# Power.net
KiCad netlist of a schematic drawn in Altium Designer
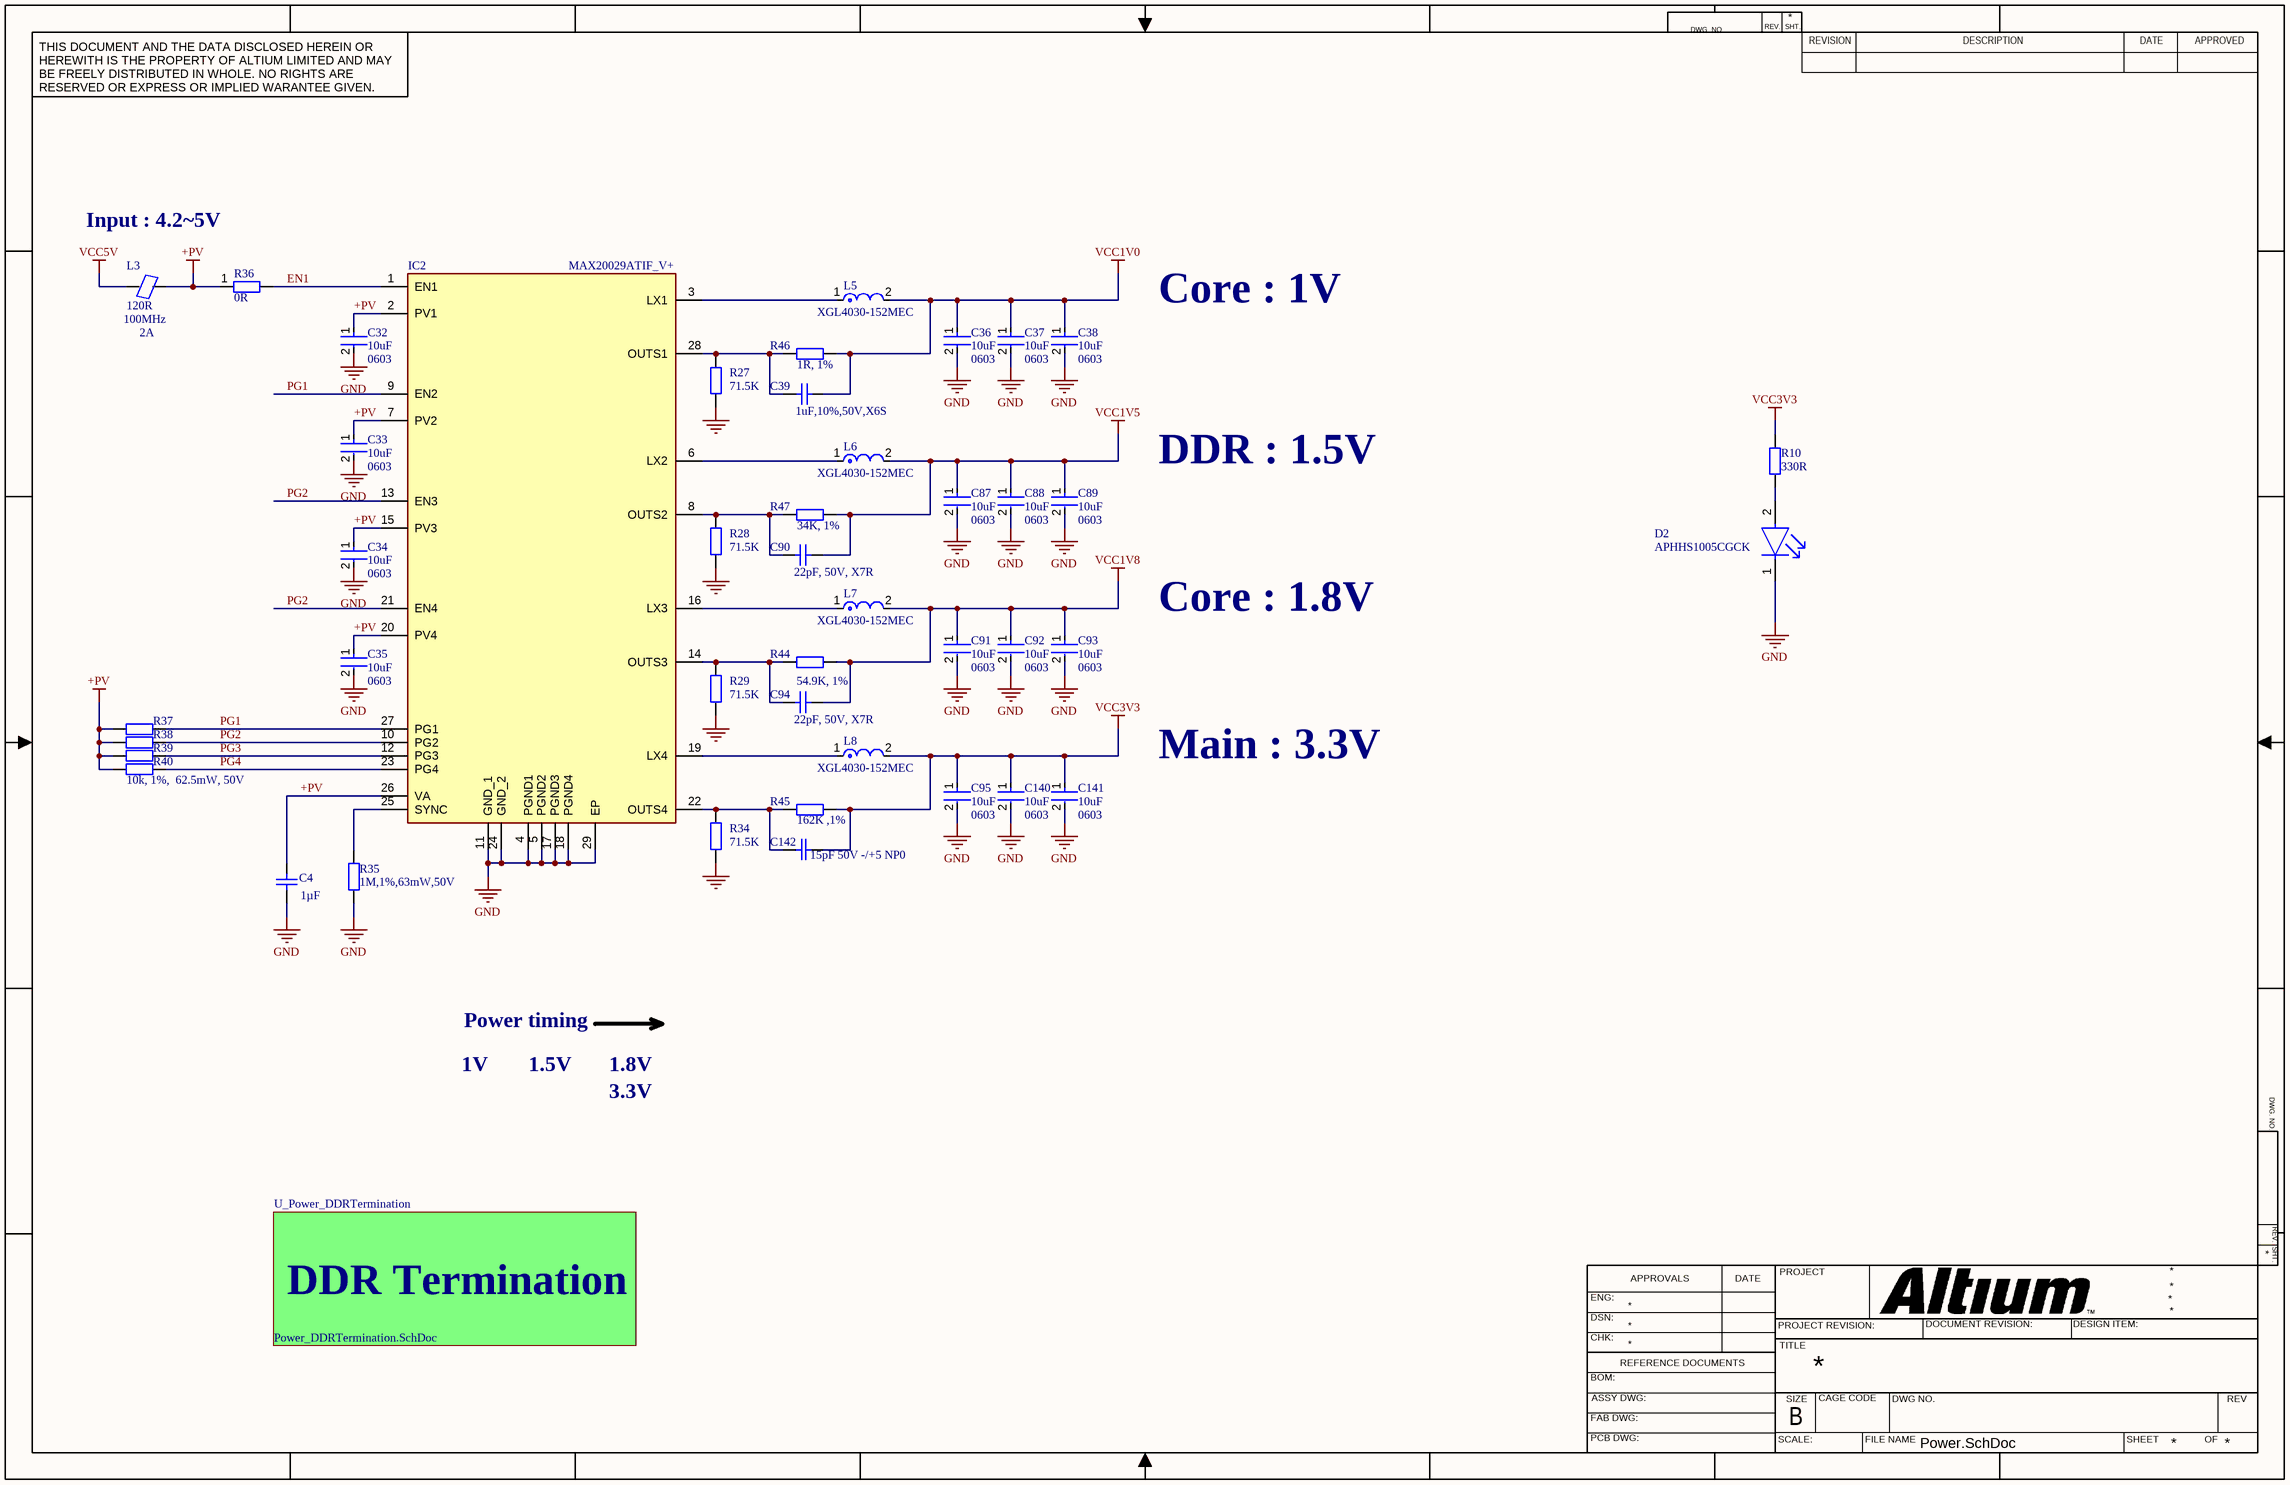
[diagram p0: Power.SchDoc]

(export (version "E")
  (design (tool "Eeschema 10.0.6"))
  (components
    (comp (ref "C4")
      (value "1µF")
      (footprint "CAP0402i")
      (description "0402, 1uF,  10%, 50V, X6S")
      (fields
        (field (name "PART NUMBER") "GRT155C81E105KE13D")
        (field (name "MANUFACTURER") "Murata")
        (field (name "CAPACITANCE") "1µF")
      )
      (libsource (lib "AmpherLib") (part "Cap_1uF_50V_X6S_0402"))
    )
    (comp (ref "C32")
      (value "GRM188R60J106ME47D")
      (footprint "FP-GRM188-0_1-e0_2_0_55-IPC_A")
      (description "Chip Multilayer Ceramic Capacitors for General Purpose, 0603, 10uF, X5R, 15%, 20%, 6.3V")
      (fields
        (field (name "CAPACITANCE") "10uF")
        (field (name "CASE/PACKAGE") "0603")
        (field (name "VOLTAGE") "6.3V")
        (field (name "TOLERANCE") "20%")
      )
      (libsource (lib "Altium Content Vault") (part "02cd4be3c70576c341d710602a673aa"))
    )
    (comp (ref "C33")
      (value "GRM188R60J106ME47D")
      (footprint "FP-GRM188-0_1-e0_2_0_55-IPC_A")
      (description "Chip Multilayer Ceramic Capacitors for General Purpose, 0603, 10uF, X5R, 15%, 20%, 6.3V")
      (fields
        (field (name "CAPACITANCE") "10uF")
        (field (name "CASE/PACKAGE") "0603")
        (field (name "VOLTAGE") "6.3V")
        (field (name "TOLERANCE") "20%")
      )
      (libsource (lib "Altium Content Vault") (part "02cd4be3c70576c341d710602a673aa"))
    )
    (comp (ref "C34")
      (value "GRM188R60J106ME47D")
      (footprint "FP-GRM188-0_1-e0_2_0_55-IPC_A")
      (description "Chip Multilayer Ceramic Capacitors for General Purpose, 0603, 10uF, X5R, 15%, 20%, 6.3V")
      (fields
        (field (name "CAPACITANCE") "10uF")
        (field (name "CASE/PACKAGE") "0603")
        (field (name "VOLTAGE") "6.3V")
        (field (name "TOLERANCE") "20%")
      )
      (libsource (lib "Altium Content Vault") (part "02cd4be3c70576c341d710602a673aa"))
    )
    (comp (ref "C35")
      (value "GRM188R60J106ME47D")
      (footprint "FP-GRM188-0_1-e0_2_0_55-IPC_A")
      (description "Chip Multilayer Ceramic Capacitors for General Purpose, 0603, 10uF, X5R, 15%, 20%, 6.3V")
      (fields
        (field (name "CAPACITANCE") "10uF")
        (field (name "CASE/PACKAGE") "0603")
        (field (name "VOLTAGE") "6.3V")
        (field (name "TOLERANCE") "20%")
      )
      (libsource (lib "Altium Content Vault") (part "02cd4be3c70576c341d710602a673aa"))
    )
    (comp (ref "C36")
      (value "GRM188R60J106ME47D")
      (footprint "FP-GRM188-0_1-e0_2_0_55-IPC_A")
      (description "Chip Multilayer Ceramic Capacitors for General Purpose, 0603, 10uF, X5R, 15%, 20%, 6.3V")
      (fields
        (field (name "CAPACITANCE") "10uF")
        (field (name "CASE/PACKAGE") "0603")
        (field (name "VOLTAGE") "6.3V")
        (field (name "TOLERANCE") "20%")
      )
      (libsource (lib "Altium Content Vault") (part "02cd4be3c70576c341d710602a673aa"))
    )
    (comp (ref "C37")
      (value "GRM188R60J106ME47D")
      (footprint "FP-GRM188-0_1-e0_2_0_55-IPC_A")
      (description "Chip Multilayer Ceramic Capacitors for General Purpose, 0603, 10uF, X5R, 15%, 20%, 6.3V")
      (fields
        (field (name "CAPACITANCE") "10uF")
        (field (name "CASE/PACKAGE") "0603")
        (field (name "VOLTAGE") "6.3V")
        (field (name "TOLERANCE") "20%")
      )
      (libsource (lib "Altium Content Vault") (part "02cd4be3c70576c341d710602a673aa"))
    )
    (comp (ref "C38")
      (value "GRM188R60J106ME47D")
      (footprint "FP-GRM188-0_1-e0_2_0_55-IPC_A")
      (description "Chip Multilayer Ceramic Capacitors for General Purpose, 0603, 10uF, X5R, 15%, 20%, 6.3V")
      (fields
        (field (name "CAPACITANCE") "10uF")
        (field (name "CASE/PACKAGE") "0603")
        (field (name "VOLTAGE") "6.3V")
        (field (name "TOLERANCE") "20%")
      )
      (libsource (lib "Altium Content Vault") (part "02cd4be3c70576c341d710602a673aa"))
    )
    (comp (ref "C39")
      (value "1uF,10%,50V,X6S")
      (footprint "CAP0402i")
      (description "0402, 1uF,  10%, 50V, X6S")
      (fields (field (name "PART NUMBER") "GRT155C81E105KE13D") (field (name "MANUFACTURER") "Murata"))
      (libsource (lib "AmpherLib") (part "Cap_1uF_50V_X6S_0402"))
    )
    (comp (ref "C87")
      (value "GRM188R60J106ME47D")
      (footprint "FP-GRM188-0_1-e0_2_0_55-IPC_A")
      (description "Chip Multilayer Ceramic Capacitors for General Purpose, 0603, 10uF, X5R, 15%, 20%, 6.3V")
      (fields
        (field (name "CAPACITANCE") "10uF")
        (field (name "CASE/PACKAGE") "0603")
        (field (name "VOLTAGE") "6.3V")
        (field (name "TOLERANCE") "20%")
      )
      (libsource (lib "Altium Content Vault") (part "02cd4be3c70576c341d710602a673aa"))
    )
    (comp (ref "C88")
      (value "GRM188R60J106ME47D")
      (footprint "FP-GRM188-0_1-e0_2_0_55-IPC_A")
      (description "Chip Multilayer Ceramic Capacitors for General Purpose, 0603, 10uF, X5R, 15%, 20%, 6.3V")
      (fields
        (field (name "CAPACITANCE") "10uF")
        (field (name "CASE/PACKAGE") "0603")
        (field (name "VOLTAGE") "6.3V")
        (field (name "TOLERANCE") "20%")
      )
      (libsource (lib "Altium Content Vault") (part "02cd4be3c70576c341d710602a673aa"))
    )
    (comp (ref "C89")
      (value "GRM188R60J106ME47D")
      (footprint "FP-GRM188-0_1-e0_2_0_55-IPC_A")
      (description "Chip Multilayer Ceramic Capacitors for General Purpose, 0603, 10uF, X5R, 15%, 20%, 6.3V")
      (fields
        (field (name "CAPACITANCE") "10uF")
        (field (name "CASE/PACKAGE") "0603")
        (field (name "VOLTAGE") "6.3V")
        (field (name "TOLERANCE") "20%")
      )
      (libsource (lib "Altium Content Vault") (part "02cd4be3c70576c341d710602a673aa"))
    )
    (comp (ref "C90")
      (value "22pF, 50V, X7R")
      (footprint "cap0402i")
      (description "Multilayer Ceramic Capacitor, AEC-Q200 CGA Series, 22 pF, - 5%, C0G / NP0, 50 V")
      (fields (field (name "TOLERANCE") "5%") (field (name "PART NUMBER") "CGA2B2C0G1H220J050BA"))
      (libsource (lib "AmpherLib") (part "CAP_22pF_50V_X7R_0402"))
    )
    (comp (ref "C91")
      (value "GRM188R60J106ME47D")
      (footprint "FP-GRM188-0_1-e0_2_0_55-IPC_A")
      (description "Chip Multilayer Ceramic Capacitors for General Purpose, 0603, 10uF, X5R, 15%, 20%, 6.3V")
      (fields
        (field (name "CAPACITANCE") "10uF")
        (field (name "CASE/PACKAGE") "0603")
        (field (name "VOLTAGE") "6.3V")
        (field (name "TOLERANCE") "20%")
      )
      (libsource (lib "Altium Content Vault") (part "02cd4be3c70576c341d710602a673aa"))
    )
    (comp (ref "C92")
      (value "GRM188R60J106ME47D")
      (footprint "FP-GRM188-0_1-e0_2_0_55-IPC_A")
      (description "Chip Multilayer Ceramic Capacitors for General Purpose, 0603, 10uF, X5R, 15%, 20%, 6.3V")
      (fields
        (field (name "CAPACITANCE") "10uF")
        (field (name "CASE/PACKAGE") "0603")
        (field (name "VOLTAGE") "6.3V")
        (field (name "TOLERANCE") "20%")
      )
      (libsource (lib "Altium Content Vault") (part "02cd4be3c70576c341d710602a673aa"))
    )
    (comp (ref "C93")
      (value "GRM188R60J106ME47D")
      (footprint "FP-GRM188-0_1-e0_2_0_55-IPC_A")
      (description "Chip Multilayer Ceramic Capacitors for General Purpose, 0603, 10uF, X5R, 15%, 20%, 6.3V")
      (fields
        (field (name "CAPACITANCE") "10uF")
        (field (name "CASE/PACKAGE") "0603")
        (field (name "VOLTAGE") "6.3V")
        (field (name "TOLERANCE") "20%")
      )
      (libsource (lib "Altium Content Vault") (part "02cd4be3c70576c341d710602a673aa"))
    )
    (comp (ref "C94")
      (value "22pF, 50V, X7R")
      (footprint "cap0402i")
      (description "Multilayer Ceramic Capacitor, AEC-Q200 CGA Series, 22 pF, - 5%, C0G / NP0, 50 V")
      (fields (field (name "TOLERANCE") "5%") (field (name "PART NUMBER") "CGA2B2C0G1H220J050BA"))
      (libsource (lib "AmpherLib") (part "CAP_22pF_50V_X7R_0402"))
    )
    (comp (ref "C95")
      (value "GRM188R60J106ME47D")
      (footprint "FP-GRM188-0_1-e0_2_0_55-IPC_A")
      (description "Chip Multilayer Ceramic Capacitors for General Purpose, 0603, 10uF, X5R, 15%, 20%, 6.3V")
      (fields
        (field (name "CAPACITANCE") "10uF")
        (field (name "CASE/PACKAGE") "0603")
        (field (name "VOLTAGE") "6.3V")
        (field (name "TOLERANCE") "20%")
      )
      (libsource (lib "Altium Content Vault") (part "02cd4be3c70576c341d710602a673aa"))
    )
    (comp (ref "C140")
      (value "GRM188R60J106ME47D")
      (footprint "FP-GRM188-0_1-e0_2_0_55-IPC_A")
      (description "Chip Multilayer Ceramic Capacitors for General Purpose, 0603, 10uF, X5R, 15%, 20%, 6.3V")
      (fields
        (field (name "CAPACITANCE") "10uF")
        (field (name "CASE/PACKAGE") "0603")
        (field (name "VOLTAGE") "6.3V")
        (field (name "TOLERANCE") "20%")
      )
      (libsource (lib "Altium Content Vault") (part "02cd4be3c70576c341d710602a673aa"))
    )
    (comp (ref "C141")
      (value "GRM188R60J106ME47D")
      (footprint "FP-GRM188-0_1-e0_2_0_55-IPC_A")
      (description "Chip Multilayer Ceramic Capacitors for General Purpose, 0603, 10uF, X5R, 15%, 20%, 6.3V")
      (fields
        (field (name "CAPACITANCE") "10uF")
        (field (name "CASE/PACKAGE") "0603")
        (field (name "VOLTAGE") "6.3V")
        (field (name "TOLERANCE") "20%")
      )
      (libsource (lib "Altium Content Vault") (part "02cd4be3c70576c341d710602a673aa"))
    )
    (comp (ref "C142")
      (value "15pF 50V -/+5 NP0")
      (footprint "CAP0402i")
      (description "0402 15 pF 50 V ±5 % Tolerance NP0 SMT Multilayer Ceramic Capacitor")
      (fields (field (name "VOLTAGE") "50V") (field (name "TOLERANCE") "5%"))
      (libsource (lib "AmpherLib") (part "Cap_15pF_50V_0402"))
    )
    (comp (ref "D2")
      (value "APHHS1005CGCK")
      (footprint "FP-APHHS1005CGCK-MFG")
      (description "LED GREEN CLEAR CHIP SMD")
      (libsource (lib "Altium Content Vault") (part "8706943c75ba83719d021d2fdc84c58"))
    )
    (comp (ref "IC2")
      (value "MAX20029ATIF_V+")
      (footprint "PCB1:QFN50P500X500X80-29N")
      (description "DC to DC Converter Quad Step-Down 3V to 5.5V Automotive 28-Pin TQFN Tube")
      (fields
        (field (name "MANUFACTURER_PART_NUMBER") "MAX20029ATIF/V+")
        (field (name "MOUSER PART NUMBER") "700-MAX20029ATIF/V+")
      )
      (libsource (lib "SamacSys") (part "MAX20029ATIF_V+"))
    )
    (comp (ref "L3")
      (value "FB_120@100MHz")
      (footprint "CAP0402i")
      (description "Ferrite Beads Multi-Layer 120Ohm 25% 100MHz 2A 0.055Ohm DCR 0402 T/R")
      (fields
        (field (name "TOLERANCE") "25%")
        (field (name "IMPEDANCE") "120R")
        (field (name "MAX DC CURRENT") "2A")
        (field (name "TEST FREQUENCY") "100MHz")
        (field (name "PART NUMBER") "BLM15PX121SN1D")
      )
      (libsource (lib "AmpherLib") (part "Ferrite Bead_ 0402_120R_100MHz_2A"))
    )
    (comp (ref "L5")
      (value "XGL4030-152MEC")
      (footprint "FP-XGL4030-MFG")
      (description "SHIELDED POWER INDUCTORS, 1.5UH")
      (libsource (lib "Altium Content Vault") (part "4cc4b267dca4c8e51f7102f422741d8"))
    )
    (comp (ref "L6")
      (value "XGL4030-152MEC")
      (footprint "FP-XGL4030-MFG")
      (description "SHIELDED POWER INDUCTORS, 1.5UH")
      (libsource (lib "Altium Content Vault") (part "4cc4b267dca4c8e51f7102f422741d8"))
    )
    (comp (ref "L7")
      (value "XGL4030-152MEC")
      (footprint "FP-XGL4030-MFG")
      (description "SHIELDED POWER INDUCTORS, 1.5UH")
      (libsource (lib "Altium Content Vault") (part "4cc4b267dca4c8e51f7102f422741d8"))
    )
    (comp (ref "L8")
      (value "XGL4030-152MEC")
      (footprint "FP-XGL4030-MFG")
      (description "SHIELDED POWER INDUCTORS, 1.5UH")
      (libsource (lib "Altium Content Vault") (part "4cc4b267dca4c8e51f7102f422741d8"))
    )
    (comp (ref "R10")
      (value "330R")
      (footprint "RES0402i")
      (description "Res Thick Film 0402 330 Ohm 1% 1/16W ±100ppm/°C Molded SMD Paper T/R")
      (fields (field (name "PART NUMBER") "CRCW0402330RFKED") (field (name "VOLTAGE") "50"))
      (libsource (lib "AmpherLib") (part "Res_330R_1%_50V_0402"))
    )
    (comp (ref "R27")
      (value "71.5K")
      (footprint "RES0402i")
      (description "Res Thick Film 0402 71.5K Ohm 1% 1/10W ±100ppm/°C Molded SMD Punched Carrier T/R")
      (fields
        (field (name "PART NUMBER") "ERJ-2RKF7152X")
        (field (name "TOLERANCE") "±1%")
        (field (name "RESISTANCE") "71.5K")
      )
      (libsource (lib "AmpherLib") (part "Res_71.5K_1%_1/10W_0402"))
    )
    (comp (ref "R28")
      (value "71.5K")
      (footprint "RES0402i")
      (description "Res Thick Film 0402 71.5K Ohm 1% 1/10W ±100ppm/°C Molded SMD Punched Carrier T/R")
      (fields
        (field (name "PART NUMBER") "ERJ-2RKF7152X")
        (field (name "TOLERANCE") "±1%")
        (field (name "RESISTANCE") "71.5K")
      )
      (libsource (lib "AmpherLib") (part "Res_71.5K_1%_1/10W_0402"))
    )
    (comp (ref "R29")
      (value "71.5K")
      (footprint "RES0402i")
      (description "Res Thick Film 0402 71.5K Ohm 1% 1/10W ±100ppm/°C Molded SMD Punched Carrier T/R")
      (fields
        (field (name "PART NUMBER") "ERJ-2RKF7152X")
        (field (name "TOLERANCE") "±1%")
        (field (name "RESISTANCE") "71.5K")
      )
      (libsource (lib "AmpherLib") (part "Res_71.5K_1%_1/10W_0402"))
    )
    (comp (ref "R34")
      (value "71.5K")
      (footprint "RES0402i")
      (description "Res Thick Film 0402 71.5K Ohm 1% 1/10W ±100ppm/°C Molded SMD Punched Carrier T/R")
      (fields
        (field (name "PART NUMBER") "ERJ-2RKF7152X")
        (field (name "TOLERANCE") "±1%")
        (field (name "RESISTANCE") "71.5K")
      )
      (libsource (lib "AmpherLib") (part "Res_71.5K_1%_1/10W_0402"))
    )
    (comp (ref "R35")
      (value "1M,1%,63mW,50V")
      (footprint "RES0402i")
      (description "0402,1M,1%,63mW,50V")
      (fields (field (name "PART NUMBER") "ERJ-2RKF1004X") (field (name "VOLTAGE") "50V"))
      (libsource (lib "AmpherLib") (part "Res_1M_1%_0402"))
    )
    (comp (ref "R36")
      (value "0R")
      (footprint "RES0402i")
      (description "0402, 0R")
      (fields (field (name "PART NUMBER") "CRCW04020000Z0EDC") (field (name "VOLTAGE") "50V"))
      (libsource (lib "AmpherLib") (part "Res_0R_0402"))
    )
    (comp (ref "R37")
      (value "10 kOhms")
      (footprint "RES0402i")
      (description "0402, 10K 1%,  62.5mW, 50V")
      (fields (field (name "PART NUMBER") "CR0402-FX-1002GLF") (field (name "VOLTAGE") "50V"))
      (libsource (lib "AmpherLib") (part "Res_10k_1%_0402"))
    )
    (comp (ref "R38")
      (value "10 kOhms")
      (footprint "RES0402i")
      (description "0402, 10K 1%,  62.5mW, 50V")
      (fields (field (name "PART NUMBER") "CR0402-FX-1002GLF") (field (name "VOLTAGE") "50V"))
      (libsource (lib "AmpherLib") (part "Res_10k_1%_0402"))
    )
    (comp (ref "R39")
      (value "10 kOhms")
      (footprint "RES0402i")
      (description "0402, 10K 1%,  62.5mW, 50V")
      (fields (field (name "PART NUMBER") "CR0402-FX-1002GLF") (field (name "VOLTAGE") "50V"))
      (libsource (lib "AmpherLib") (part "Res_10k_1%_0402"))
    )
    (comp (ref "R40")
      (value "10k, 1%,  62.5mW, 50V")
      (footprint "RES0402i")
      (description "0402, 10K 1%,  62.5mW, 50V")
      (fields (field (name "PART NUMBER") "CR0402-FX-1002GLF") (field (name "VOLTAGE") "50V"))
      (libsource (lib "AmpherLib") (part "Res_10k_1%_0402"))
    )
    (comp (ref "R44")
      (value "54.9K, 1%")
      (footprint "RES0402i")
      (description "SMD Chip Resistor, 54.9 kOhm, ± 1%, 100 mW, 0402 [1005 Metric], Thick Film, Precision")
      (fields (field (name "TOLERANCE") "±1%") (field (name "MANUFACTURER") "Panasonic"))
      (libsource (lib "AmpherLib") (part "Res_A_0402__________________________Template_1_1_1_1_1"))
    )
    (comp (ref "R45")
      (value "162K ,1%")
      (footprint "RES0402i")
      (description "Res Thick Film 0402 162K Ohm 1% 0.1W ±100ppm/°C Molded SMD Punched Carrier T/R")
      (fields (field (name "TOLERANCE") "±1%") (field (name "MANUFACTURER") "Panasonic"))
      (libsource (lib "AmpherLib") (part "Res_A_0402__________________________Template_1_1_1_1_1"))
    )
    (comp (ref "R46")
      (value "1R, 1%")
      (footprint "RES0402i")
      (description "SMD Chip Resistor, 1 Ohm, ± 5%, 63 mW, 0402 [1005 Metric], Thick Film, General Purpose")
      (fields (field (name "TOLERANCE") "±1%") (field (name "MANUFACTURER") "Vishay Dale"))
      (libsource (lib "AmpherLib") (part "Res_A_0402__________________________Template_1_1_1_1_1"))
    )
    (comp (ref "R47")
      (value "34K, 1%")
      (footprint "RES0402i")
      (description "SMD Chip Resistor, 34 kOhm, ± 1%, 63 mW, 0402 [1005 Metric], Thick Film, General Purpose")
      (fields (field (name "TOLERANCE") "±1%") (field (name "MANUFACTURER") "Vishay"))
      (libsource (lib "AmpherLib") (part "Res_A_0402__________________________Template_1_1_1_1_1"))
    )
  )
  (nets
    (net (code "1") (name "+PV") (class "Default")
      (node (ref "C32") (pin "1") (pinfunction "1_1") (pintype "passive"))
      (node (ref "C33") (pin "1") (pinfunction "1_1") (pintype "passive"))
      (node (ref "C34") (pin "1") (pinfunction "1_1") (pintype "passive"))
      (node (ref "C35") (pin "1") (pinfunction "1_1") (pintype "passive"))
      (node (ref "C4") (pin "2") (pinfunction "2_2") (pintype "passive"))
      (node (ref "IC2") (pin "15") (pinfunction "PV3_15") (pintype "passive"))
      (node (ref "IC2") (pin "2") (pinfunction "PV1_2") (pintype "passive"))
      (node (ref "IC2") (pin "20") (pinfunction "PV4_20") (pintype "passive"))
      (node (ref "IC2") (pin "26") (pinfunction "VA_26") (pintype "passive"))
      (node (ref "IC2") (pin "7") (pinfunction "PV2_7") (pintype "passive"))
      (node (ref "L3") (pin "2") (pinfunction "2_2") (pintype "passive"))
      (node (ref "R36") (pin "1") (pinfunction "1_1") (pintype "passive"))
      (node (ref "R37") (pin "1") (pinfunction "1_1") (pintype "passive"))
      (node (ref "R38") (pin "1") (pinfunction "1_1") (pintype "passive"))
      (node (ref "R39") (pin "1") (pinfunction "1_1") (pintype "passive"))
      (node (ref "R40") (pin "1") (pinfunction "1_1") (pintype "passive"))
    )
    (net (code "2") (name "/EN1") (class "Default")
      (node (ref "IC2") (pin "1") (pinfunction "EN1_1") (pintype "passive"))
      (node (ref "R36") (pin "2") (pinfunction "2_2") (pintype "passive"))
    )
    (net (code "3") (name "/PG1") (class "Default")
      (node (ref "IC2") (pin "27") (pinfunction "PG1_27") (pintype "passive"))
      (node (ref "IC2") (pin "9") (pinfunction "EN2_9") (pintype "passive"))
      (node (ref "R37") (pin "2") (pinfunction "2_2") (pintype "passive"))
    )
    (net (code "4") (name "/PG2") (class "Default")
      (node (ref "IC2") (pin "10") (pinfunction "PG2_10") (pintype "passive"))
      (node (ref "IC2") (pin "13") (pinfunction "EN3_13") (pintype "passive"))
      (node (ref "IC2") (pin "21") (pinfunction "EN4_21") (pintype "passive"))
      (node (ref "R38") (pin "2") (pinfunction "2_2") (pintype "passive"))
    )
    (net (code "5") (name "/PG3") (class "Default")
      (node (ref "IC2") (pin "12") (pinfunction "PG3_12") (pintype "passive"))
      (node (ref "R39") (pin "2") (pinfunction "2_2") (pintype "passive"))
    )
    (net (code "6") (name "/PG4") (class "Default")
      (node (ref "IC2") (pin "23") (pinfunction "PG4_23") (pintype "passive"))
      (node (ref "R40") (pin "2") (pinfunction "2_2") (pintype "passive"))
    )
    (net (code "7") (name "GND") (class "Default")
      (node (ref "C140") (pin "2") (pinfunction "2_2") (pintype "passive"))
      (node (ref "C141") (pin "2") (pinfunction "2_2") (pintype "passive"))
      (node (ref "C32") (pin "2") (pinfunction "2_2") (pintype "passive"))
      (node (ref "C33") (pin "2") (pinfunction "2_2") (pintype "passive"))
      (node (ref "C34") (pin "2") (pinfunction "2_2") (pintype "passive"))
      (node (ref "C35") (pin "2") (pinfunction "2_2") (pintype "passive"))
      (node (ref "C36") (pin "2") (pinfunction "2_2") (pintype "passive"))
      (node (ref "C37") (pin "2") (pinfunction "2_2") (pintype "passive"))
      (node (ref "C38") (pin "2") (pinfunction "2_2") (pintype "passive"))
      (node (ref "C4") (pin "1") (pinfunction "1_1") (pintype "passive"))
      (node (ref "C87") (pin "2") (pinfunction "2_2") (pintype "passive"))
      (node (ref "C88") (pin "2") (pinfunction "2_2") (pintype "passive"))
      (node (ref "C89") (pin "2") (pinfunction "2_2") (pintype "passive"))
      (node (ref "C91") (pin "2") (pinfunction "2_2") (pintype "passive"))
      (node (ref "C92") (pin "2") (pinfunction "2_2") (pintype "passive"))
      (node (ref "C93") (pin "2") (pinfunction "2_2") (pintype "passive"))
      (node (ref "C95") (pin "2") (pinfunction "2_2") (pintype "passive"))
      (node (ref "D2") (pin "1") (pinfunction "C_1") (pintype "passive"))
      (node (ref "IC2") (pin "11") (pinfunction "GND_1_11") (pintype "passive"))
      (node (ref "IC2") (pin "17") (pinfunction "PGND3_17") (pintype "passive"))
      (node (ref "IC2") (pin "18") (pinfunction "PGND4_18") (pintype "passive"))
      (node (ref "IC2") (pin "24") (pinfunction "GND_2_24") (pintype "passive"))
      (node (ref "IC2") (pin "29") (pinfunction "EP_29") (pintype "passive"))
      (node (ref "IC2") (pin "4") (pinfunction "PGND1_4") (pintype "passive"))
      (node (ref "IC2") (pin "5") (pinfunction "PGND2_5") (pintype "passive"))
      (node (ref "R27") (pin "1") (pinfunction "1_1") (pintype "passive"))
      (node (ref "R28") (pin "1") (pinfunction "1_1") (pintype "passive"))
      (node (ref "R29") (pin "1") (pinfunction "1_1") (pintype "passive"))
      (node (ref "R34") (pin "1") (pinfunction "1_1") (pintype "passive"))
      (node (ref "R35") (pin "1") (pinfunction "1_1") (pintype "passive"))
    )
    (net (code "8") (name "Net-(D2-A)") (class "Default")
      (node (ref "D2") (pin "2") (pinfunction "A_2") (pintype "passive"))
      (node (ref "R10") (pin "1") (pinfunction "1_1") (pintype "passive"))
    )
    (net (code "9") (name "Net-(IC2-LX1)") (class "Default")
      (node (ref "IC2") (pin "3") (pinfunction "LX1_3") (pintype "passive"))
      (node (ref "L5") (pin "1") (pinfunction "1_1") (pintype "passive"))
    )
    (net (code "10") (name "Net-(IC2-LX2)") (class "Default")
      (node (ref "IC2") (pin "6") (pinfunction "LX2_6") (pintype "passive"))
      (node (ref "L6") (pin "1") (pinfunction "1_1") (pintype "passive"))
    )
    (net (code "11") (name "Net-(IC2-LX3)") (class "Default")
      (node (ref "IC2") (pin "16") (pinfunction "LX3_16") (pintype "passive"))
      (node (ref "L7") (pin "1") (pinfunction "1_1") (pintype "passive"))
    )
    (net (code "12") (name "Net-(IC2-LX4)") (class "Default")
      (node (ref "IC2") (pin "19") (pinfunction "LX4_19") (pintype "passive"))
      (node (ref "L8") (pin "1") (pinfunction "1_1") (pintype "passive"))
    )
    (net (code "13") (name "Net-(IC2-OUTS1)") (class "Default")
      (node (ref "C39") (pin "1") (pinfunction "1_1") (pintype "passive"))
      (node (ref "IC2") (pin "28") (pinfunction "OUTS1_28") (pintype "passive"))
      (node (ref "R27") (pin "2") (pinfunction "2_2") (pintype "passive"))
      (node (ref "R46") (pin "1") (pinfunction "1_1") (pintype "passive"))
    )
    (net (code "14") (name "Net-(IC2-OUTS2)") (class "Default")
      (node (ref "C90") (pin "1") (pinfunction "1_1") (pintype "passive"))
      (node (ref "IC2") (pin "8") (pinfunction "OUTS2_8") (pintype "passive"))
      (node (ref "R28") (pin "2") (pinfunction "2_2") (pintype "passive"))
      (node (ref "R47") (pin "1") (pinfunction "1_1") (pintype "passive"))
    )
    (net (code "15") (name "Net-(IC2-OUTS3)") (class "Default")
      (node (ref "C94") (pin "1") (pinfunction "1_1") (pintype "passive"))
      (node (ref "IC2") (pin "14") (pinfunction "OUTS3_14") (pintype "passive"))
      (node (ref "R29") (pin "2") (pinfunction "2_2") (pintype "passive"))
      (node (ref "R44") (pin "1") (pinfunction "1_1") (pintype "passive"))
    )
    (net (code "16") (name "Net-(IC2-OUTS4)") (class "Default")
      (node (ref "C142") (pin "2") (pinfunction "2_2") (pintype "passive"))
      (node (ref "IC2") (pin "22") (pinfunction "OUTS4_22") (pintype "passive"))
      (node (ref "R34") (pin "2") (pinfunction "2_2") (pintype "passive"))
      (node (ref "R45") (pin "1") (pinfunction "1_1") (pintype "passive"))
    )
    (net (code "17") (name "Net-(IC2-SYNC)") (class "Default")
      (node (ref "IC2") (pin "25") (pinfunction "SYNC_25") (pintype "passive"))
      (node (ref "R35") (pin "2") (pinfunction "2_2") (pintype "passive"))
    )
    (net (code "18") (name "VCC1V0") (class "Default")
      (node (ref "C36") (pin "1") (pinfunction "1_1") (pintype "passive"))
      (node (ref "C37") (pin "1") (pinfunction "1_1") (pintype "passive"))
      (node (ref "C38") (pin "1") (pinfunction "1_1") (pintype "passive"))
      (node (ref "C39") (pin "2") (pinfunction "2_2") (pintype "passive"))
      (node (ref "L5") (pin "2") (pinfunction "2_2") (pintype "passive"))
      (node (ref "R46") (pin "2") (pinfunction "2_2") (pintype "passive"))
    )
    (net (code "19") (name "VCC1V5") (class "Default")
      (node (ref "C87") (pin "1") (pinfunction "1_1") (pintype "passive"))
      (node (ref "C88") (pin "1") (pinfunction "1_1") (pintype "passive"))
      (node (ref "C89") (pin "1") (pinfunction "1_1") (pintype "passive"))
      (node (ref "C90") (pin "2") (pinfunction "2_2") (pintype "passive"))
      (node (ref "L6") (pin "2") (pinfunction "2_2") (pintype "passive"))
      (node (ref "R47") (pin "2") (pinfunction "2_2") (pintype "passive"))
    )
    (net (code "20") (name "VCC1V8") (class "Default")
      (node (ref "C91") (pin "1") (pinfunction "1_1") (pintype "passive"))
      (node (ref "C92") (pin "1") (pinfunction "1_1") (pintype "passive"))
      (node (ref "C93") (pin "1") (pinfunction "1_1") (pintype "passive"))
      (node (ref "C94") (pin "2") (pinfunction "2_2") (pintype "passive"))
      (node (ref "L7") (pin "2") (pinfunction "2_2") (pintype "passive"))
      (node (ref "R44") (pin "2") (pinfunction "2_2") (pintype "passive"))
    )
    (net (code "21") (name "VCC3V3") (class "Default")
      (node (ref "C140") (pin "1") (pinfunction "1_1") (pintype "passive"))
      (node (ref "C141") (pin "1") (pinfunction "1_1") (pintype "passive"))
      (node (ref "C142") (pin "1") (pinfunction "1_1") (pintype "passive"))
      (node (ref "C95") (pin "1") (pinfunction "1_1") (pintype "passive"))
      (node (ref "L8") (pin "2") (pinfunction "2_2") (pintype "passive"))
      (node (ref "R10") (pin "2") (pinfunction "2_2") (pintype "passive"))
      (node (ref "R45") (pin "2") (pinfunction "2_2") (pintype "passive"))
    )
    (net (code "22") (name "VCC5V") (class "Default")
      (node (ref "L3") (pin "1") (pinfunction "1_1") (pintype "passive"))
    )
  )
)
